# Sheet1.net
KiCad netlist of a schematic drawn in Altium Designer
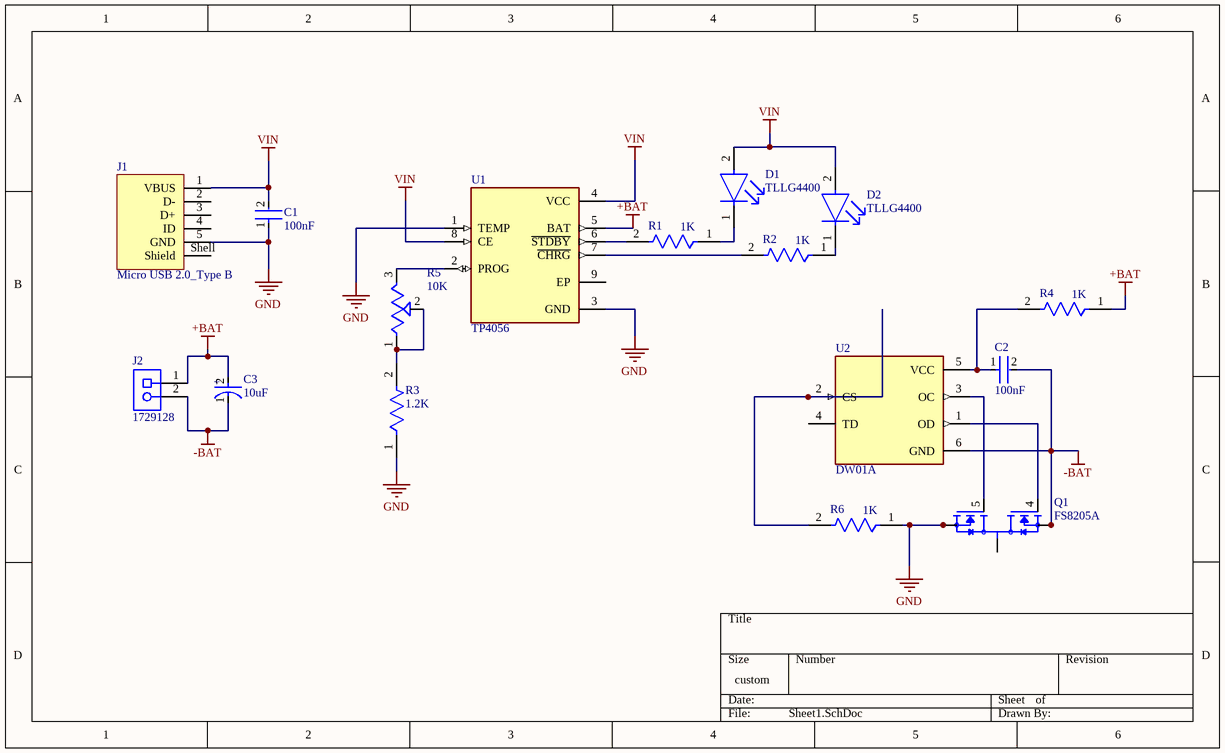
[diagram p0: Sheet1.SchDoc]

(export (version "E")
  (design (tool "Eeschema 10.0.6"))
  (components
    (comp (ref "C1")
      (value "100nF")
      (footprint "FP-K15H5-MFG")
      (description "CAP CER 0.1UF 50V X7R RADIAL")
      (fields (field (name "TOLERANCE") "10%") (field (name "VOLTAGE") "50V"))
      (libsource (lib "Altium Content Vault") (part "02cd4be3c70576c341d710602a673aa"))
    )
    (comp (ref "C2")
      (value "100nF")
      (footprint "FP-K15H5-MFG")
      (description "CAP CER 0.1UF 50V X7R RADIAL")
      (fields (field (name "TOLERANCE") "10%") (field (name "VOLTAGE") "50V"))
      (libsource (lib "Altium Content Vault") (part "02cd4be3c70576c341d710602a673aa"))
    )
    (comp (ref "C3")
      (value "10uF")
      (footprint "FP-ECE-A1HN100U-MFG")
      (description "CAP ALUM 10UF 20% 50V RADIAL")
      (fields (field (name "VOLTAGE") "50V") (field (name "TOLERANCE") "20%"))
      (libsource (lib "Altium Content Vault") (part "cf48714ba7e38822c1575c7ec0b6d1f"))
    )
    (comp (ref "D1")
      (value "TLLG4400")
      (footprint "FP-6_544-5255_01-4-MFG")
      (description "TLLG4400 Led, Pcb, Green, 0.63MCD, 3MM, T-1, 7MA, 1.9V, 565NM, 25DEG, 20V, 20MW, -40")
      (libsource (lib "Altium Content Vault") (part "8706943c75ba83719d021d2fdc84c58"))
    )
    (comp (ref "D2")
      (value "TLLG4400")
      (footprint "FP-6_544-5255_01-4-MFG")
      (description "TLLG4400 Led, Pcb, Green, 0.63MCD, 3MM, T-1, 7MA, 1.9V, 565NM, 25DEG, 20V, 20MW, -40")
      (libsource (lib "Altium Content Vault") (part "8706943c75ba83719d021d2fdc84c58"))
    )
    (comp (ref "J1")
      (value "Micro USB 2.0_Type B")
      (footprint "Micro USB 2.0_Type B")
      (libsource (lib "YoussifLIB") (part "Micro USB 2.0_Type B"))
    )
    (comp (ref "J2")
      (value "1729128")
      (footprint "PHOE-1729128-2_V")
      (description "PCB Terminal Block, 13.5 A, 400 V, 2-Pin THD, RoHS, Bulk")
      (fields (field (name "MANUFACTURER") "Phoenix Contact"))
      (libsource (lib "Altium Content Vault") (part "CN-2P-F-R2"))
    )
    (comp (ref "Q1")
      (value "FS8205A")
      (footprint "SOP65P640X120-8N")
      (fields (field (name "MF") "Fortune Semiconductor"))
      (libsource (lib "YoussifLIB") (part "FS8205A"))
    )
    (comp (ref "R1")
      (value "1K")
      (footprint "FP-MRS25-MFG")
      (description "RES 1K OHM 0.6W 1% AXIAL")
      (fields (field (name "TOLERANCE") "1%"))
      (libsource (lib "Altium Content Vault") (part "1029c3af85768c4190bb7ad29bc67b5"))
    )
    (comp (ref "R2")
      (value "1K")
      (footprint "FP-MRS25-MFG")
      (description "RES 1K OHM 0.6W 1% AXIAL")
      (fields (field (name "TOLERANCE") "1%"))
      (libsource (lib "Altium Content Vault") (part "1029c3af85768c4190bb7ad29bc67b5"))
    )
    (comp (ref "R3")
      (value "1.2K")
      (footprint "FP-MRS25-MFG")
      (description "RES 1K OHM 0.6W 1% AXIAL")
      (fields (field (name "TOLERANCE") "1%"))
      (libsource (lib "Altium Content Vault") (part "1029c3af85768c4190bb7ad29bc67b5"))
    )
    (comp (ref "R4")
      (value "1K")
      (footprint "FP-MRS25-MFG")
      (description "RES 1K OHM 0.6W 1% AXIAL")
      (fields (field (name "TOLERANCE") "1%"))
      (libsource (lib "Altium Content Vault") (part "1029c3af85768c4190bb7ad29bc67b5"))
    )
    (comp (ref "R5")
      (value "10K")
      (footprint "TRIM_3318F-1-502")
      (description "5 kOhms 0.1W, 1/10W PC Pins Through Hole Trimmer Potentiometer Carbon 1.0 Turn Top Adjustment")
      (fields (field (name "MP") "3318F-1-502") (field (name "MF") "Bourns Inc."))
      (libsource (lib "YoussifLIB") (part "Carbon Trimmer"))
    )
    (comp (ref "R6")
      (value "1K")
      (footprint "FP-MRS25-MFG")
      (description "RES 1K OHM 0.6W 1% AXIAL")
      (fields (field (name "TOLERANCE") "1%"))
      (libsource (lib "Altium Content Vault") (part "1029c3af85768c4190bb7ad29bc67b5"))
    )
    (comp (ref "U1")
      (value "TP4056")
      (footprint "TP4056")
      (description "Complete single cell Li-Ion battery with a constant current / constant voltage linear charger")
      (fields (field (name "MF") "NanJing Top Power ASIC Corp."))
      (libsource (lib "YoussifLIB") (part "TP4056"))
    )
    (comp (ref "U2")
      (value "DW01A")
      (footprint "SOT95P280X145-6N")
      (description "One Cell Lithium-ion/Polymer Battery Protection IC")
      (fields (field (name "MF") "Fortune Semiconductor"))
      (libsource (lib "YoussifLIB") (part "DW01A"))
    )
  )
  (nets
    (net (code "1") (name "+BAT") (class "Default")
      (node (ref "C3") (pin "2") (pinfunction "A_2") (pintype "passive"))
      (node (ref "J2") (pin "1") (pinfunction "1_1") (pintype "passive"))
      (node (ref "R4") (pin "1") (pinfunction "1_1") (pintype "passive"))
      (node (ref "U1") (pin "5") (pinfunction "BAT_5") (pintype "output"))
    )
    (net (code "2") (name "-BAT") (class "Default")
      (node (ref "C2") (pin "2") (pinfunction "2_2") (pintype "passive"))
      (node (ref "C3") (pin "1") (pinfunction "C_1") (pintype "passive"))
      (node (ref "J2") (pin "2") (pinfunction "2_2") (pintype "passive"))
      (node (ref "Q1") (pin "2") (pinfunction "S1_2") (pintype "passive"))
      (node (ref "Q1") (pin "3") (pinfunction "S1_3") (pintype "passive"))
      (node (ref "U2") (pin "6") (pinfunction "GND_6") (pintype "power_in"))
    )
    (net (code "3") (name "GND") (class "Default")
      (node (ref "C1") (pin "1") (pinfunction "1_1") (pintype "passive"))
      (node (ref "J1") (pin "5") (pinfunction "GND_5") (pintype "passive"))
      (node (ref "Q1") (pin "6") (pinfunction "S2_6") (pintype "passive"))
      (node (ref "Q1") (pin "7") (pinfunction "S2_7") (pintype "passive"))
      (node (ref "R3") (pin "1") (pinfunction "1_1") (pintype "passive"))
      (node (ref "R6") (pin "1") (pinfunction "1_1") (pintype "passive"))
      (node (ref "U1") (pin "1") (pinfunction "TEMP_1") (pintype "input"))
      (node (ref "U1") (pin "3") (pinfunction "GND_3") (pintype "power_in"))
    )
    (net (code "4") (name "Net-(D1-C)") (class "Default")
      (node (ref "D1") (pin "1") (pinfunction "C_1") (pintype "passive"))
      (node (ref "R1") (pin "1") (pinfunction "1_1") (pintype "passive"))
    )
    (net (code "5") (name "Net-(D2-C)") (class "Default")
      (node (ref "D2") (pin "1") (pinfunction "C_1") (pintype "passive"))
      (node (ref "R2") (pin "1") (pinfunction "1_1") (pintype "passive"))
    )
    (net (code "6") (name "Net-(Q1-D12-Pad1)") (class "Default")
      (node (ref "Q1") (pin "1") (pinfunction "D12_1") (pintype "passive"))
      (node (ref "Q1") (pin "8") (pinfunction "D12_8") (pintype "passive"))
    )
    (net (code "7") (name "Net-(Q1-G1)") (class "Default")
      (node (ref "Q1") (pin "4") (pinfunction "G1_4") (pintype "passive"))
      (node (ref "U2") (pin "1") (pinfunction "OD_1") (pintype "output"))
    )
    (net (code "8") (name "Net-(Q1-G2)") (class "Default")
      (node (ref "Q1") (pin "5") (pinfunction "G2_5") (pintype "passive"))
      (node (ref "U2") (pin "3") (pinfunction "OC_3") (pintype "output"))
    )
    (net (code "9") (name "Net-(R5-CCW)") (class "Default")
      (node (ref "R3") (pin "2") (pinfunction "2_2") (pintype "passive"))
      (node (ref "R5") (pin "1") (pinfunction "CCW_1") (pintype "passive"))
      (node (ref "R5") (pin "2") (pinfunction "WIPER_2") (pintype "passive"))
    )
    (net (code "10") (name "Net-(R5-CW)") (class "Default")
      (node (ref "R5") (pin "3") (pinfunction "CW_3") (pintype "passive"))
      (node (ref "U1") (pin "2") (pinfunction "PROG_2") (pintype "bidirectional"))
    )
    (net (code "11") (name "Net-(U1-~{CHRG})") (class "Default")
      (node (ref "R2") (pin "2") (pinfunction "2_2") (pintype "passive"))
      (node (ref "U1") (pin "7") (pinfunction "~{CHRG}_7") (pintype "output"))
    )
    (net (code "12") (name "Net-(U1-~{STDBY})") (class "Default")
      (node (ref "R1") (pin "2") (pinfunction "2_2") (pintype "passive"))
      (node (ref "U1") (pin "6") (pinfunction "~{STDBY}_6") (pintype "output"))
    )
    (net (code "13") (name "Net-(U2-CS)") (class "Default")
      (node (ref "R6") (pin "2") (pinfunction "2_2") (pintype "passive"))
      (node (ref "U2") (pin "2") (pinfunction "CS_2") (pintype "input"))
    )
    (net (code "14") (name "Net-(U2-VCC)") (class "Default")
      (node (ref "C2") (pin "1") (pinfunction "1_1") (pintype "passive"))
      (node (ref "R4") (pin "2") (pinfunction "2_2") (pintype "passive"))
      (node (ref "U2") (pin "5") (pinfunction "VCC_5") (pintype "power_in"))
    )
    (net (code "15") (name "VIN") (class "Default")
      (node (ref "C1") (pin "2") (pinfunction "2_2") (pintype "passive"))
      (node (ref "D1") (pin "2") (pinfunction "A_2") (pintype "passive"))
      (node (ref "D2") (pin "2") (pinfunction "A_2") (pintype "passive"))
      (node (ref "J1") (pin "1") (pinfunction "VBUS_1") (pintype "passive"))
      (node (ref "U1") (pin "4") (pinfunction "VCC_4") (pintype "power_in"))
      (node (ref "U1") (pin "8") (pinfunction "CE_8") (pintype "input"))
    )
    (net (code "16") (name "unconnected-(J1-D+-Pad3)") (class "Default")
      (node (ref "J1") (pin "3") (pinfunction "D+_3") (pintype "passive"))
    )
    (net (code "17") (name "unconnected-(J1-D--Pad2)") (class "Default")
      (node (ref "J1") (pin "2") (pinfunction "D-_2") (pintype "passive"))
    )
    (net (code "18") (name "unconnected-(J1-ID-Pad4)") (class "Default")
      (node (ref "J1") (pin "4") (pinfunction "ID_4") (pintype "passive"))
    )
    (net (code "19") (name "unconnected-(J1-Shield-PadShell)") (class "Default")
      (node (ref "J1") (pin "Shell") (pinfunction "Shield_Shell") (pintype "passive"))
    )
    (net (code "20") (name "unconnected-(U1-EP-Pad9)") (class "Default")
      (node (ref "U1") (pin "9") (pinfunction "EP_9") (pintype "passive"))
    )
    (net (code "21") (name "unconnected-(U2-TD-Pad4)") (class "Default")
      (node (ref "U2") (pin "4") (pinfunction "TD_4") (pintype "passive"))
    )
  )
)
